# module_SX1278_type2.net
KiCad netlist of a schematic drawn in EAGLE
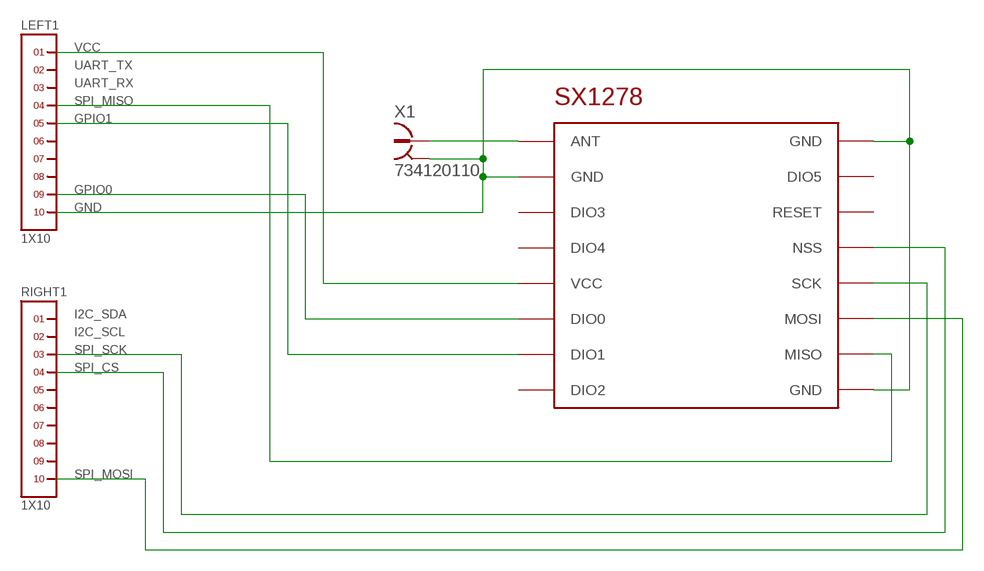
[diagram p0: schematic, sheet 1]

(export (version "E")
  (design (tool "Eeschema 10.0.6"))
  (components
    (comp (ref "LEFT1")
      (value "1X10")
      (footprint "eagle-import:1X10")
      (libsource (lib "eagle-import") (part "1X10"))
    )
    (comp (ref "RIGHT1")
      (value "1X10")
      (footprint "eagle-import:1X10")
      (libsource (lib "eagle-import") (part "1X10"))
    )
    (comp (ref "U$1")
      (value "SX1278_2")
      (footprint "eagle-import:SX1278_2")
      (libsource (lib "eagle-import") (part "SX1278_2"))
    )
    (comp (ref "X1")
      (value "734120110")
      (footprint "eagle-import:734120110")
      (libsource (lib "eagle-import") (part "734120110"))
    )
  )
  (nets
    (net (code "1") (name "Net-(LEFT1-Pad1)") (class "Default")
      (node (ref "LEFT1") (pin "1") (pinfunction "1_1") (pintype "bidirectional"))
      (node (ref "U$1") (pin "VCC") (pinfunction "VCC_VCC") (pintype "bidirectional"))
    )
    (net (code "2") (name "Net-(LEFT1-Pad4)") (class "Default")
      (node (ref "LEFT1") (pin "4") (pinfunction "4_4") (pintype "bidirectional"))
      (node (ref "U$1") (pin "MISO") (pinfunction "MISO_MISO") (pintype "bidirectional"))
    )
    (net (code "3") (name "Net-(LEFT1-Pad5)") (class "Default")
      (node (ref "LEFT1") (pin "5") (pinfunction "5_5") (pintype "bidirectional"))
      (node (ref "U$1") (pin "DIO1") (pinfunction "DIO1_DIO1") (pintype "bidirectional"))
    )
    (net (code "4") (name "Net-(LEFT1-Pad9)") (class "Default")
      (node (ref "LEFT1") (pin "9") (pinfunction "9_9") (pintype "bidirectional"))
      (node (ref "U$1") (pin "DIO0") (pinfunction "DIO0_DIO0") (pintype "bidirectional"))
    )
    (net (code "5") (name "Net-(LEFT1-Pad10)") (class "Default")
      (node (ref "LEFT1") (pin "10") (pinfunction "10_10") (pintype "bidirectional"))
      (node (ref "U$1") (pin "GND@1") (pinfunction "GND_GND@1") (pintype "bidirectional"))
      (node (ref "U$1") (pin "GND@2") (pinfunction "GND_GND@2") (pintype "bidirectional"))
      (node (ref "U$1") (pin "GND@3") (pinfunction "GND_GND@3") (pintype "bidirectional"))
      (node (ref "X1") (pin "S@1") (pinfunction "2_S@1") (pintype "passive"))
      (node (ref "X1") (pin "S@2") (pinfunction "2_S@2") (pintype "passive"))
      (node (ref "X1") (pin "S@3") (pinfunction "2_S@3") (pintype "passive"))
    )
    (net (code "6") (name "Net-(RIGHT1-Pad3)") (class "Default")
      (node (ref "RIGHT1") (pin "3") (pinfunction "3_3") (pintype "bidirectional"))
      (node (ref "U$1") (pin "SCK") (pinfunction "SCK_SCK") (pintype "bidirectional"))
    )
    (net (code "7") (name "Net-(RIGHT1-Pad4)") (class "Default")
      (node (ref "RIGHT1") (pin "4") (pinfunction "4_4") (pintype "bidirectional"))
      (node (ref "U$1") (pin "NSS") (pinfunction "NSS_NSS") (pintype "bidirectional"))
    )
    (net (code "8") (name "Net-(RIGHT1-Pad10)") (class "Default")
      (node (ref "RIGHT1") (pin "10") (pinfunction "10_10") (pintype "bidirectional"))
      (node (ref "U$1") (pin "MOSI") (pinfunction "MOSI_MOSI") (pintype "bidirectional"))
    )
    (net (code "9") (name "Net-(U$1-PadANT)") (class "Default")
      (node (ref "U$1") (pin "ANT") (pinfunction "ANT_ANT") (pintype "bidirectional"))
      (node (ref "X1") (pin "1") (pinfunction "1_1") (pintype "passive"))
    )
    (net (code "10") (name "unconnected-(LEFT1-Pad2)") (class "Default")
      (node (ref "LEFT1") (pin "2") (pinfunction "2_2") (pintype "bidirectional"))
    )
    (net (code "11") (name "unconnected-(LEFT1-Pad3)") (class "Default")
      (node (ref "LEFT1") (pin "3") (pinfunction "3_3") (pintype "bidirectional"))
    )
    (net (code "12") (name "unconnected-(LEFT1-Pad6)") (class "Default")
      (node (ref "LEFT1") (pin "6") (pinfunction "6_6") (pintype "bidirectional"))
    )
    (net (code "13") (name "unconnected-(LEFT1-Pad7)") (class "Default")
      (node (ref "LEFT1") (pin "7") (pinfunction "7_7") (pintype "bidirectional"))
    )
    (net (code "14") (name "unconnected-(LEFT1-Pad8)") (class "Default")
      (node (ref "LEFT1") (pin "8") (pinfunction "8_8") (pintype "bidirectional"))
    )
    (net (code "15") (name "unconnected-(RIGHT1-Pad1)") (class "Default")
      (node (ref "RIGHT1") (pin "1") (pinfunction "1_1") (pintype "bidirectional"))
    )
    (net (code "16") (name "unconnected-(RIGHT1-Pad2)") (class "Default")
      (node (ref "RIGHT1") (pin "2") (pinfunction "2_2") (pintype "bidirectional"))
    )
    (net (code "17") (name "unconnected-(RIGHT1-Pad5)") (class "Default")
      (node (ref "RIGHT1") (pin "5") (pinfunction "5_5") (pintype "bidirectional"))
    )
    (net (code "18") (name "unconnected-(RIGHT1-Pad6)") (class "Default")
      (node (ref "RIGHT1") (pin "6") (pinfunction "6_6") (pintype "bidirectional"))
    )
    (net (code "19") (name "unconnected-(RIGHT1-Pad7)") (class "Default")
      (node (ref "RIGHT1") (pin "7") (pinfunction "7_7") (pintype "bidirectional"))
    )
    (net (code "20") (name "unconnected-(RIGHT1-Pad8)") (class "Default")
      (node (ref "RIGHT1") (pin "8") (pinfunction "8_8") (pintype "bidirectional"))
    )
    (net (code "21") (name "unconnected-(RIGHT1-Pad9)") (class "Default")
      (node (ref "RIGHT1") (pin "9") (pinfunction "9_9") (pintype "bidirectional"))
    )
    (net (code "22") (name "unconnected-(U$1-PadDIO2)") (class "Default")
      (node (ref "U$1") (pin "DIO2") (pinfunction "DIO2_DIO2") (pintype "bidirectional"))
    )
    (net (code "23") (name "unconnected-(U$1-PadDIO3)") (class "Default")
      (node (ref "U$1") (pin "DIO3") (pinfunction "DIO3_DIO3") (pintype "bidirectional"))
    )
    (net (code "24") (name "unconnected-(U$1-PadDIO4)") (class "Default")
      (node (ref "U$1") (pin "DIO4") (pinfunction "DIO4_DIO4") (pintype "bidirectional"))
    )
    (net (code "25") (name "unconnected-(U$1-PadDIO5)") (class "Default")
      (node (ref "U$1") (pin "DIO5") (pinfunction "DIO5_DIO5") (pintype "bidirectional"))
    )
    (net (code "26") (name "unconnected-(U$1-PadRESET)") (class "Default")
      (node (ref "U$1") (pin "RESET") (pinfunction "RESET_RESET") (pintype "bidirectional"))
    )
  )
)
